# SUP_1_2_1_8.net
KiCad netlist of a schematic drawn in Altium Designer
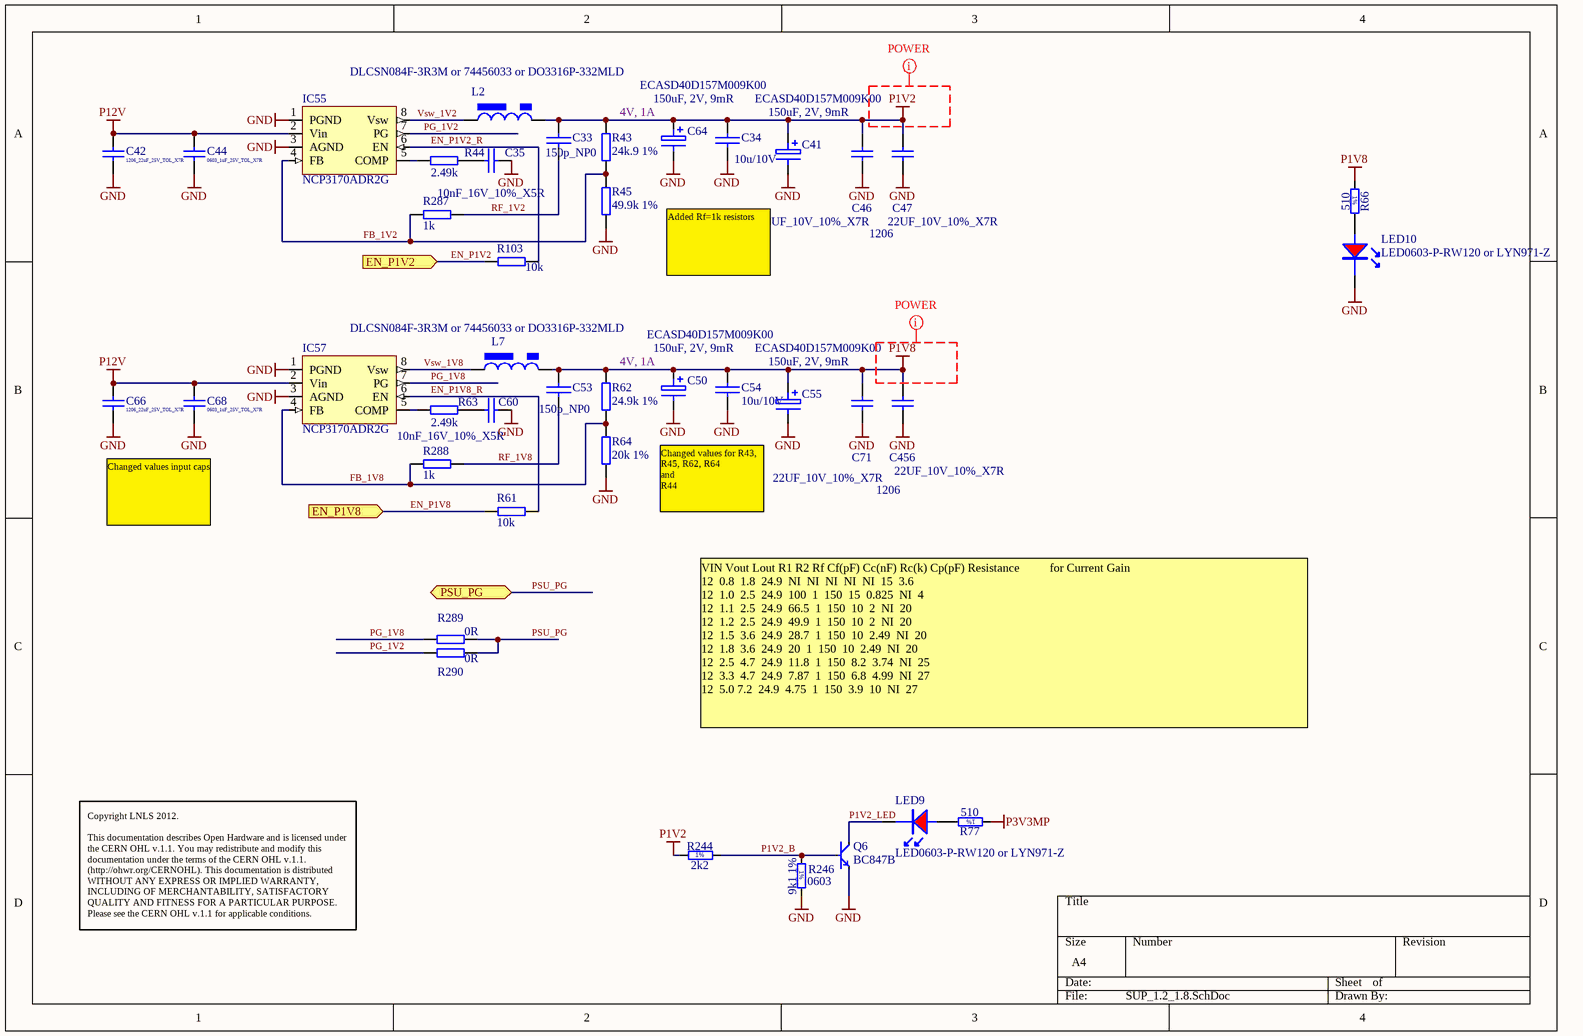
[diagram p0: SUP_1.2_1.8.SchDoc]

(export (version "E")
  (design (tool "Eeschema 10.0.6"))
  (components
    (comp (ref "C33")
      (value "150p_NP0")
      (footprint "0603C")
      (description "Capacitor SMD")
      (libsource (lib "LIBRARY_SCH") (part "CAP_SMD_0603"))
    )
    (comp (ref "C34")
      (value "10u/10V")
      (footprint "0805C")
      (description "Capacitor SMD")
      (libsource (lib "LIBRARY_SCH") (part "CAP_SMD_0805"))
    )
    (comp (ref "C35")
      (value "10nF_16V_10%_X5R")
      (footprint "0603C")
      (description "Capacitor SMD")
      (libsource (lib "LIBRARY_SCH") (part "CAP_SMD_0603"))
    )
    (comp (ref "C41")
      (value "ECASD40D157M009K00")
      (footprint "2917_POLY")
      (description "POLY, 150uF, 2V, ESR: 9mR")
      (fields (field (name "ALTIUM_VALUE") "150uF, 2V, 9mR"))
      (libsource (lib "LIBRARY_SCH") (part "CAP_POLYMER_SMDD"))
    )
    (comp (ref "C42")
      (value "1206_22uF_25V_TOL_X7R")
      (footprint "CAPC3225X140N")
      (fields (field (name "PART NUMBER") "Ceramic_1206"))
      (libsource (lib "Capacitors") (part "Capacitor"))
    )
    (comp (ref "C44")
      (value "0603_1uF_25V_TOL_X7R")
      (footprint "CAPC1608X90N")
      (fields (field (name "PART NUMBER") "Ceramic_0603"))
      (libsource (lib "Capacitors") (part "Capacitor"))
    )
    (comp (ref "C46")
      (value "22UF_10V_10%_X7R")
      (footprint "1206C")
      (description "Non-polarised capacitor")
      (fields
        (field (name "PART NUMBER") "CC1206_22UF_10V_10%_X7R")
        (field (name "VOLTAGE") "10V")
        (field (name "AUTHOR") "CERN DEM JLC")
      )
      (libsource (lib "Capacitors") (part "Capacitor - non polarized"))
    )
    (comp (ref "C47")
      (value "22UF_10V_10%_X7R")
      (footprint "1206C")
      (description "Non-polarised capacitor")
      (fields
        (field (name "PART NUMBER") "CC1206_22UF_10V_10%_X7R")
        (field (name "VOLTAGE") "10V")
        (field (name "CASE") "1206")
        (field (name "AUTHOR") "CERN DEM JLC")
      )
      (libsource (lib "Capacitors") (part "Capacitor - non polarized"))
    )
    (comp (ref "C50")
      (value "ECASD40D157M009K00")
      (footprint "2917_POLY")
      (description "POLY, 150uF, 2V, ESR: 9mR")
      (fields (field (name "ALTIUM_VALUE") "150uF, 2V, 9mR"))
      (libsource (lib "LIBRARY_SCH") (part "CAP_POLYMER_SMDD"))
    )
    (comp (ref "C53")
      (value "150p_NP0")
      (footprint "0603C")
      (description "Capacitor SMD")
      (libsource (lib "LIBRARY_SCH") (part "CAP_SMD_0603"))
    )
    (comp (ref "C54")
      (value "10u/10V")
      (footprint "0805C")
      (description "Capacitor SMD")
      (libsource (lib "LIBRARY_SCH") (part "CAP_SMD_0805"))
    )
    (comp (ref "C55")
      (value "ECASD40D157M009K00")
      (footprint "2917_POLY")
      (description "POLY, 150uF, 2V, ESR: 9mR")
      (fields (field (name "ALTIUM_VALUE") "150uF, 2V, 9mR"))
      (libsource (lib "LIBRARY_SCH") (part "CAP_POLYMER_SMDD"))
    )
    (comp (ref "C60")
      (value "10nF_16V_10%_X5R")
      (footprint "0603C")
      (description "Capacitor SMD")
      (libsource (lib "LIBRARY_SCH") (part "CAP_SMD_0603"))
    )
    (comp (ref "C64")
      (value "ECASD40D157M009K00")
      (footprint "2917_POLY")
      (description "POLY, 150uF, 2V, ESR: 9mR")
      (fields (field (name "ALTIUM_VALUE") "150uF, 2V, 9mR"))
      (libsource (lib "LIBRARY_SCH") (part "CAP_POLYMER_SMDD"))
    )
    (comp (ref "C66")
      (value "1206_22uF_25V_TOL_X7R")
      (footprint "CAPC3225X140N")
      (fields (field (name "PART NUMBER") "Ceramic_1206"))
      (libsource (lib "Capacitors") (part "Capacitor"))
    )
    (comp (ref "C68")
      (value "0603_1uF_25V_TOL_X7R")
      (footprint "CAPC1608X90N")
      (fields (field (name "PART NUMBER") "Ceramic_0603"))
      (libsource (lib "Capacitors") (part "Capacitor"))
    )
    (comp (ref "C71")
      (value "22UF_10V_10%_X7R")
      (footprint "1206C")
      (description "Non-polarised capacitor")
      (fields
        (field (name "PART NUMBER") "CC1206_22UF_10V_10%_X7R")
        (field (name "VOLTAGE") "10V")
        (field (name "AUTHOR") "CERN DEM JLC")
      )
      (libsource (lib "Capacitors") (part "Capacitor - non polarized"))
    )
    (comp (ref "C456")
      (value "22UF_10V_10%_X7R")
      (footprint "1206C")
      (description "Non-polarised capacitor")
      (fields
        (field (name "PART NUMBER") "CC1206_22UF_10V_10%_X7R")
        (field (name "VOLTAGE") "10V")
        (field (name "CASE") "1206")
        (field (name "AUTHOR") "CERN DEM JLC")
      )
      (libsource (lib "Capacitors") (part "Capacitor - non polarized"))
    )
    (comp (ref "IC55")
      (value "NCP3170ADR2G")
      (footprint "so-8")
      (description "4.5V to 18V, 3A synch buck")
      (libsource (lib "LIBRARY_SCH") (part "PWM_NCP3170"))
    )
    (comp (ref "IC57")
      (value "NCP3170ADR2G")
      (footprint "so-8")
      (description "4.5V to 18V, 3A synch buck")
      (libsource (lib "LIBRARY_SCH") (part "PWM_NCP3170"))
    )
    (comp (ref "L2")
      (value "DLCSN084F-3R3M or 74456033 or DO3316P-332MLD")
      (footprint "IND_CSN084F")
      (description "3.3uH, 20%, 5.4A, 0.015R")
      (libsource (lib "LIBRARY_SCH") (part "L_POWER_CSN084F_3R3"))
    )
    (comp (ref "L7")
      (value "DLCSN084F-3R3M or 74456033 or DO3316P-332MLD")
      (footprint "IND_CSN084F")
      (description "3.3uH, 20%, 5.4A, 0.015R")
      (libsource (lib "LIBRARY_SCH") (part "L_POWER_CSN084F_3R3"))
    )
    (comp (ref "LED9")
      (value "LED0603-P-RW120 or LYN971-Z")
      (footprint "led_0603R")
      (description "LED 0603 red")
      (libsource (lib "LIBRARY_SCH") (part "LED_0603R"))
    )
    (comp (ref "LED10")
      (value "LED0603-P-RW120 or LYN971-Z")
      (footprint "led_0603R")
      (description "LED 0603 red")
      (libsource (lib "LIBRARY_SCH") (part "LED_0603R"))
    )
    (comp (ref "Q6")
      (value "BC847B")
      (footprint "SOT-23")
      (description "Transistor")
      (libsource (lib "LIBRARY_SCH") (part "Q_BC847B"))
    )
    (comp (ref "R43")
      (value "24k.9 1%")
      (footprint "0603R")
      (description "SMD Resistor")
      (libsource (lib "LIBRARY_SCH") (part "RES_0603"))
    )
    (comp (ref "R44")
      (value "2.49k")
      (footprint "0603R")
      (description "SMD Resistor")
      (libsource (lib "LIBRARY_SCH") (part "RES_0603"))
    )
    (comp (ref "R45")
      (value "49.9k 1%")
      (footprint "0603R")
      (description "SMD Resistor")
      (libsource (lib "LIBRARY_SCH") (part "RES_0603"))
    )
    (comp (ref "R61")
      (value "10k")
      (footprint "0402R")
      (description "SMD Resistor")
      (libsource (lib "LIBRARY_SCH") (part "RES_SMD"))
    )
    (comp (ref "R62")
      (value "24.9k 1%")
      (footprint "0603R")
      (description "SMD Resistor")
      (libsource (lib "LIBRARY_SCH") (part "RES_0603"))
    )
    (comp (ref "R63")
      (value "2.49k")
      (footprint "0603R")
      (description "SMD Resistor")
      (libsource (lib "LIBRARY_SCH") (part "RES_0603"))
    )
    (comp (ref "R64")
      (value "20k 1%")
      (footprint "0603R")
      (description "SMD Resistor")
      (libsource (lib "LIBRARY_SCH") (part "RES_0603"))
    )
    (comp (ref "R66")
      (value "510")
      (footprint "0603R")
      (description "Resistor - 1%")
      (fields
        (field (name "PART NUMBER") "R0402_510R_1%_0.0625W_100PPM")
        (field (name "POWER") "0.0625W")
        (field (name "AUTHOR") "CERN DEM JLC")
      )
      (libsource (lib "Resistors") (part "Resistor - 1%"))
    )
    (comp (ref "R77")
      (value "510")
      (footprint "0603R")
      (description "Resistor - 1%")
      (fields
        (field (name "PART NUMBER") "R0402_510R_1%_0.0625W_100PPM")
        (field (name "POWER") "0.0625W")
        (field (name "AUTHOR") "CERN DEM JLC")
      )
      (libsource (lib "Resistors") (part "Resistor - 1%"))
    )
    (comp (ref "R103")
      (value "10k")
      (footprint "0402R")
      (description "SMD Resistor")
      (libsource (lib "LIBRARY_SCH") (part "RES_SMD"))
    )
    (comp (ref "R244")
      (value "2k2")
      (footprint "RESC1608X55N")
      (description "Resistor - 1%")
      (fields
        (field (name "PART NUMBER") "R0603_2K2_1%_0.1W_100PPM")
        (field (name "POWER") "0.1W")
        (field (name "AUTHOR") "CERN DEM JLC")
      )
      (libsource (lib "Resistors") (part "Resistor - 1%"))
    )
    (comp (ref "R246")
      (value "9k1 1%")
      (footprint "0603R")
      (description "Resistor - 1%")
      (fields
        (field (name "PART NUMBER") "R0603_9K1_1%_0.1W_100PPM")
        (field (name "POWER") "0.1W")
        (field (name "CASE") "0603")
        (field (name "AUTHOR") "CERN DEM JLC")
      )
      (libsource (lib "Resistors") (part "Resistor - 1%"))
    )
    (comp (ref "R287")
      (value "1k")
      (footprint "0603R")
      (description "SMD Resistor")
      (libsource (lib "LIBRARY_SCH") (part "RES_0603"))
    )
    (comp (ref "R288")
      (value "1k")
      (footprint "0603R")
      (description "SMD Resistor")
      (libsource (lib "LIBRARY_SCH") (part "RES_0603"))
    )
    (comp (ref "R289")
      (value "0R")
      (footprint "0402R")
      (description "SMD Resistor")
      (libsource (lib "LIBRARY_SCH") (part "RES_0402"))
    )
    (comp (ref "R290")
      (value "0R")
      (footprint "0402R")
      (description "SMD Resistor")
      (libsource (lib "LIBRARY_SCH") (part "RES_0402"))
    )
  )
  (nets
    (net (code "1") (name "/EN_P1V2") (class "Default")
      (node (ref "R103") (pin "1") (pinfunction "1_1") (pintype "passive"))
    )
    (net (code "2") (name "/EN_P1V2_R") (class "Default")
      (node (ref "IC55") (pin "6") (pinfunction "EN_6") (pintype "input"))
      (node (ref "R103") (pin "2") (pinfunction "2_2") (pintype "passive"))
    )
    (net (code "3") (name "/EN_P1V8") (class "Default")
      (node (ref "R61") (pin "1") (pinfunction "1_1") (pintype "passive"))
    )
    (net (code "4") (name "/EN_P1V8_R") (class "Default")
      (node (ref "IC57") (pin "6") (pinfunction "EN_6") (pintype "input"))
      (node (ref "R61") (pin "2") (pinfunction "2_2") (pintype "passive"))
    )
    (net (code "5") (name "/FB_1V2") (class "Default")
      (node (ref "IC55") (pin "4") (pinfunction "FB_4") (pintype "input"))
      (node (ref "R287") (pin "2") (pinfunction "2_2") (pintype "passive"))
      (node (ref "R43") (pin "1") (pinfunction "1_1") (pintype "passive"))
      (node (ref "R45") (pin "2") (pinfunction "2_2") (pintype "passive"))
    )
    (net (code "6") (name "/FB_1V8") (class "Default")
      (node (ref "IC57") (pin "4") (pinfunction "FB_4") (pintype "input"))
      (node (ref "R288") (pin "2") (pinfunction "2_2") (pintype "passive"))
      (node (ref "R62") (pin "1") (pinfunction "1_1") (pintype "passive"))
      (node (ref "R64") (pin "2") (pinfunction "2_2") (pintype "passive"))
    )
    (net (code "7") (name "/P1V2_B") (class "Default")
      (node (ref "Q6") (pin "1") (pinfunction "B_1") (pintype "passive"))
      (node (ref "R244") (pin "2") (pinfunction "2_2") (pintype "passive"))
      (node (ref "R246") (pin "1") (pinfunction "1_1") (pintype "passive"))
    )
    (net (code "8") (name "/P1V2_LED") (class "Default")
      (node (ref "LED9") (pin "K") (pinfunction "K_K") (pintype "passive"))
      (node (ref "Q6") (pin "3") (pinfunction "C_3") (pintype "passive"))
    )
    (net (code "9") (name "/PG_1V2") (class "Default")
      (node (ref "IC55") (pin "7") (pinfunction "PG_7") (pintype "output"))
      (node (ref "R290") (pin "2") (pinfunction "2_2") (pintype "passive"))
    )
    (net (code "10") (name "/PG_1V8") (class "Default")
      (node (ref "IC57") (pin "7") (pinfunction "PG_7") (pintype "output"))
      (node (ref "R289") (pin "2") (pinfunction "2_2") (pintype "passive"))
    )
    (net (code "11") (name "/PSU_PG") (class "Default")
      (node (ref "R289") (pin "1") (pinfunction "1_1") (pintype "passive"))
      (node (ref "R290") (pin "1") (pinfunction "1_1") (pintype "passive"))
    )
    (net (code "12") (name "/RF_1V2") (class "Default")
      (node (ref "C33") (pin "2") (pinfunction "2_2") (pintype "passive"))
      (node (ref "R287") (pin "1") (pinfunction "1_1") (pintype "passive"))
    )
    (net (code "13") (name "/RF_1V8") (class "Default")
      (node (ref "C53") (pin "2") (pinfunction "2_2") (pintype "passive"))
      (node (ref "R288") (pin "1") (pinfunction "1_1") (pintype "passive"))
    )
    (net (code "14") (name "/Vsw_1V2") (class "Default")
      (node (ref "IC55") (pin "8") (pinfunction "Vsw_8") (pintype "output"))
      (node (ref "L2") (pin "1") (pintype "passive"))
    )
    (net (code "15") (name "/Vsw_1V8") (class "Default")
      (node (ref "IC57") (pin "8") (pinfunction "Vsw_8") (pintype "output"))
      (node (ref "L7") (pin "1") (pintype "passive"))
    )
    (net (code "16") (name "GND") (class "Default")
      (node (ref "C34") (pin "2") (pinfunction "2_2") (pintype "passive"))
      (node (ref "C35") (pin "2") (pinfunction "2_2") (pintype "passive"))
      (node (ref "C41") (pin "2") (pinfunction "2_2") (pintype "passive"))
      (node (ref "C42") (pin "1") (pinfunction "1_1") (pintype "passive"))
      (node (ref "C44") (pin "1") (pinfunction "1_1") (pintype "passive"))
      (node (ref "C456") (pin "2") (pinfunction "2_2") (pintype "passive"))
      (node (ref "C46") (pin "2") (pinfunction "2_2") (pintype "passive"))
      (node (ref "C47") (pin "2") (pinfunction "2_2") (pintype "passive"))
      (node (ref "C50") (pin "2") (pinfunction "2_2") (pintype "passive"))
      (node (ref "C54") (pin "2") (pinfunction "2_2") (pintype "passive"))
      (node (ref "C55") (pin "2") (pinfunction "2_2") (pintype "passive"))
      (node (ref "C60") (pin "2") (pinfunction "2_2") (pintype "passive"))
      (node (ref "C64") (pin "2") (pinfunction "2_2") (pintype "passive"))
      (node (ref "C66") (pin "1") (pinfunction "1_1") (pintype "passive"))
      (node (ref "C68") (pin "1") (pinfunction "1_1") (pintype "passive"))
      (node (ref "C71") (pin "2") (pinfunction "2_2") (pintype "passive"))
      (node (ref "IC55") (pin "1") (pinfunction "PGND_1") (pintype "power_in"))
      (node (ref "IC55") (pin "3") (pinfunction "AGND_3") (pintype "power_in"))
      (node (ref "IC57") (pin "1") (pinfunction "PGND_1") (pintype "power_in"))
      (node (ref "IC57") (pin "3") (pinfunction "AGND_3") (pintype "power_in"))
      (node (ref "LED10") (pin "K") (pinfunction "K_K") (pintype "passive"))
      (node (ref "Q6") (pin "2") (pinfunction "E_2") (pintype "passive"))
      (node (ref "R246") (pin "2") (pinfunction "2_2") (pintype "passive"))
      (node (ref "R45") (pin "1") (pinfunction "1_1") (pintype "passive"))
      (node (ref "R64") (pin "1") (pinfunction "1_1") (pintype "passive"))
    )
    (net (code "17") (name "Net-(C35-Pad1)") (class "Default")
      (node (ref "C35") (pin "1") (pinfunction "1_1") (pintype "passive"))
      (node (ref "R44") (pin "1") (pinfunction "1_1") (pintype "passive"))
    )
    (net (code "18") (name "Net-(C60-Pad1)") (class "Default")
      (node (ref "C60") (pin "1") (pinfunction "1_1") (pintype "passive"))
      (node (ref "R63") (pin "1") (pinfunction "1_1") (pintype "passive"))
    )
    (net (code "19") (name "Net-(IC55-COMP)") (class "Default")
      (node (ref "IC55") (pin "5") (pinfunction "COMP_5") (pintype "passive"))
      (node (ref "R44") (pin "2") (pinfunction "2_2") (pintype "passive"))
    )
    (net (code "20") (name "Net-(IC57-COMP)") (class "Default")
      (node (ref "IC57") (pin "5") (pinfunction "COMP_5") (pintype "passive"))
      (node (ref "R63") (pin "2") (pinfunction "2_2") (pintype "passive"))
    )
    (net (code "21") (name "Net-(LED9-PadA)") (class "Default")
      (node (ref "LED9") (pin "A") (pinfunction "A_A") (pintype "passive"))
      (node (ref "R77") (pin "2") (pinfunction "2_2") (pintype "passive"))
    )
    (net (code "22") (name "Net-(LED10-PadA)") (class "Default")
      (node (ref "LED10") (pin "A") (pinfunction "A_A") (pintype "passive"))
      (node (ref "R66") (pin "2") (pinfunction "2_2") (pintype "passive"))
    )
    (net (code "23") (name "P1V2") (class "Default")
      (node (ref "C33") (pin "1") (pinfunction "1_1") (pintype "passive"))
      (node (ref "C34") (pin "1") (pinfunction "1_1") (pintype "passive"))
      (node (ref "C41") (pin "1") (pinfunction "1_1") (pintype "passive"))
      (node (ref "C46") (pin "1") (pinfunction "1_1") (pintype "passive"))
      (node (ref "C47") (pin "1") (pinfunction "1_1") (pintype "passive"))
      (node (ref "C64") (pin "1") (pinfunction "1_1") (pintype "passive"))
      (node (ref "L2") (pin "2") (pintype "passive"))
      (node (ref "R244") (pin "1") (pinfunction "1_1") (pintype "passive"))
      (node (ref "R43") (pin "2") (pinfunction "2_2") (pintype "passive"))
    )
    (net (code "24") (name "P1V8") (class "Default")
      (node (ref "C456") (pin "1") (pinfunction "1_1") (pintype "passive"))
      (node (ref "C50") (pin "1") (pinfunction "1_1") (pintype "passive"))
      (node (ref "C53") (pin "1") (pinfunction "1_1") (pintype "passive"))
      (node (ref "C54") (pin "1") (pinfunction "1_1") (pintype "passive"))
      (node (ref "C55") (pin "1") (pinfunction "1_1") (pintype "passive"))
      (node (ref "C71") (pin "1") (pinfunction "1_1") (pintype "passive"))
      (node (ref "L7") (pin "2") (pintype "passive"))
      (node (ref "R62") (pin "2") (pinfunction "2_2") (pintype "passive"))
      (node (ref "R66") (pin "1") (pinfunction "1_1") (pintype "passive"))
    )
    (net (code "25") (name "P3V3MP") (class "Default")
      (node (ref "R77") (pin "1") (pinfunction "1_1") (pintype "passive"))
    )
    (net (code "26") (name "P12V") (class "Default")
      (node (ref "C42") (pin "2") (pinfunction "2_2") (pintype "passive"))
      (node (ref "C44") (pin "2") (pinfunction "2_2") (pintype "passive"))
      (node (ref "C66") (pin "2") (pinfunction "2_2") (pintype "passive"))
      (node (ref "C68") (pin "2") (pinfunction "2_2") (pintype "passive"))
      (node (ref "IC55") (pin "2") (pinfunction "Vin_2") (pintype "power_in"))
      (node (ref "IC57") (pin "2") (pinfunction "Vin_2") (pintype "power_in"))
    )
  )
)
